# LOOP_DAC.net
KiCad netlist of a schematic drawn in Altium Designer
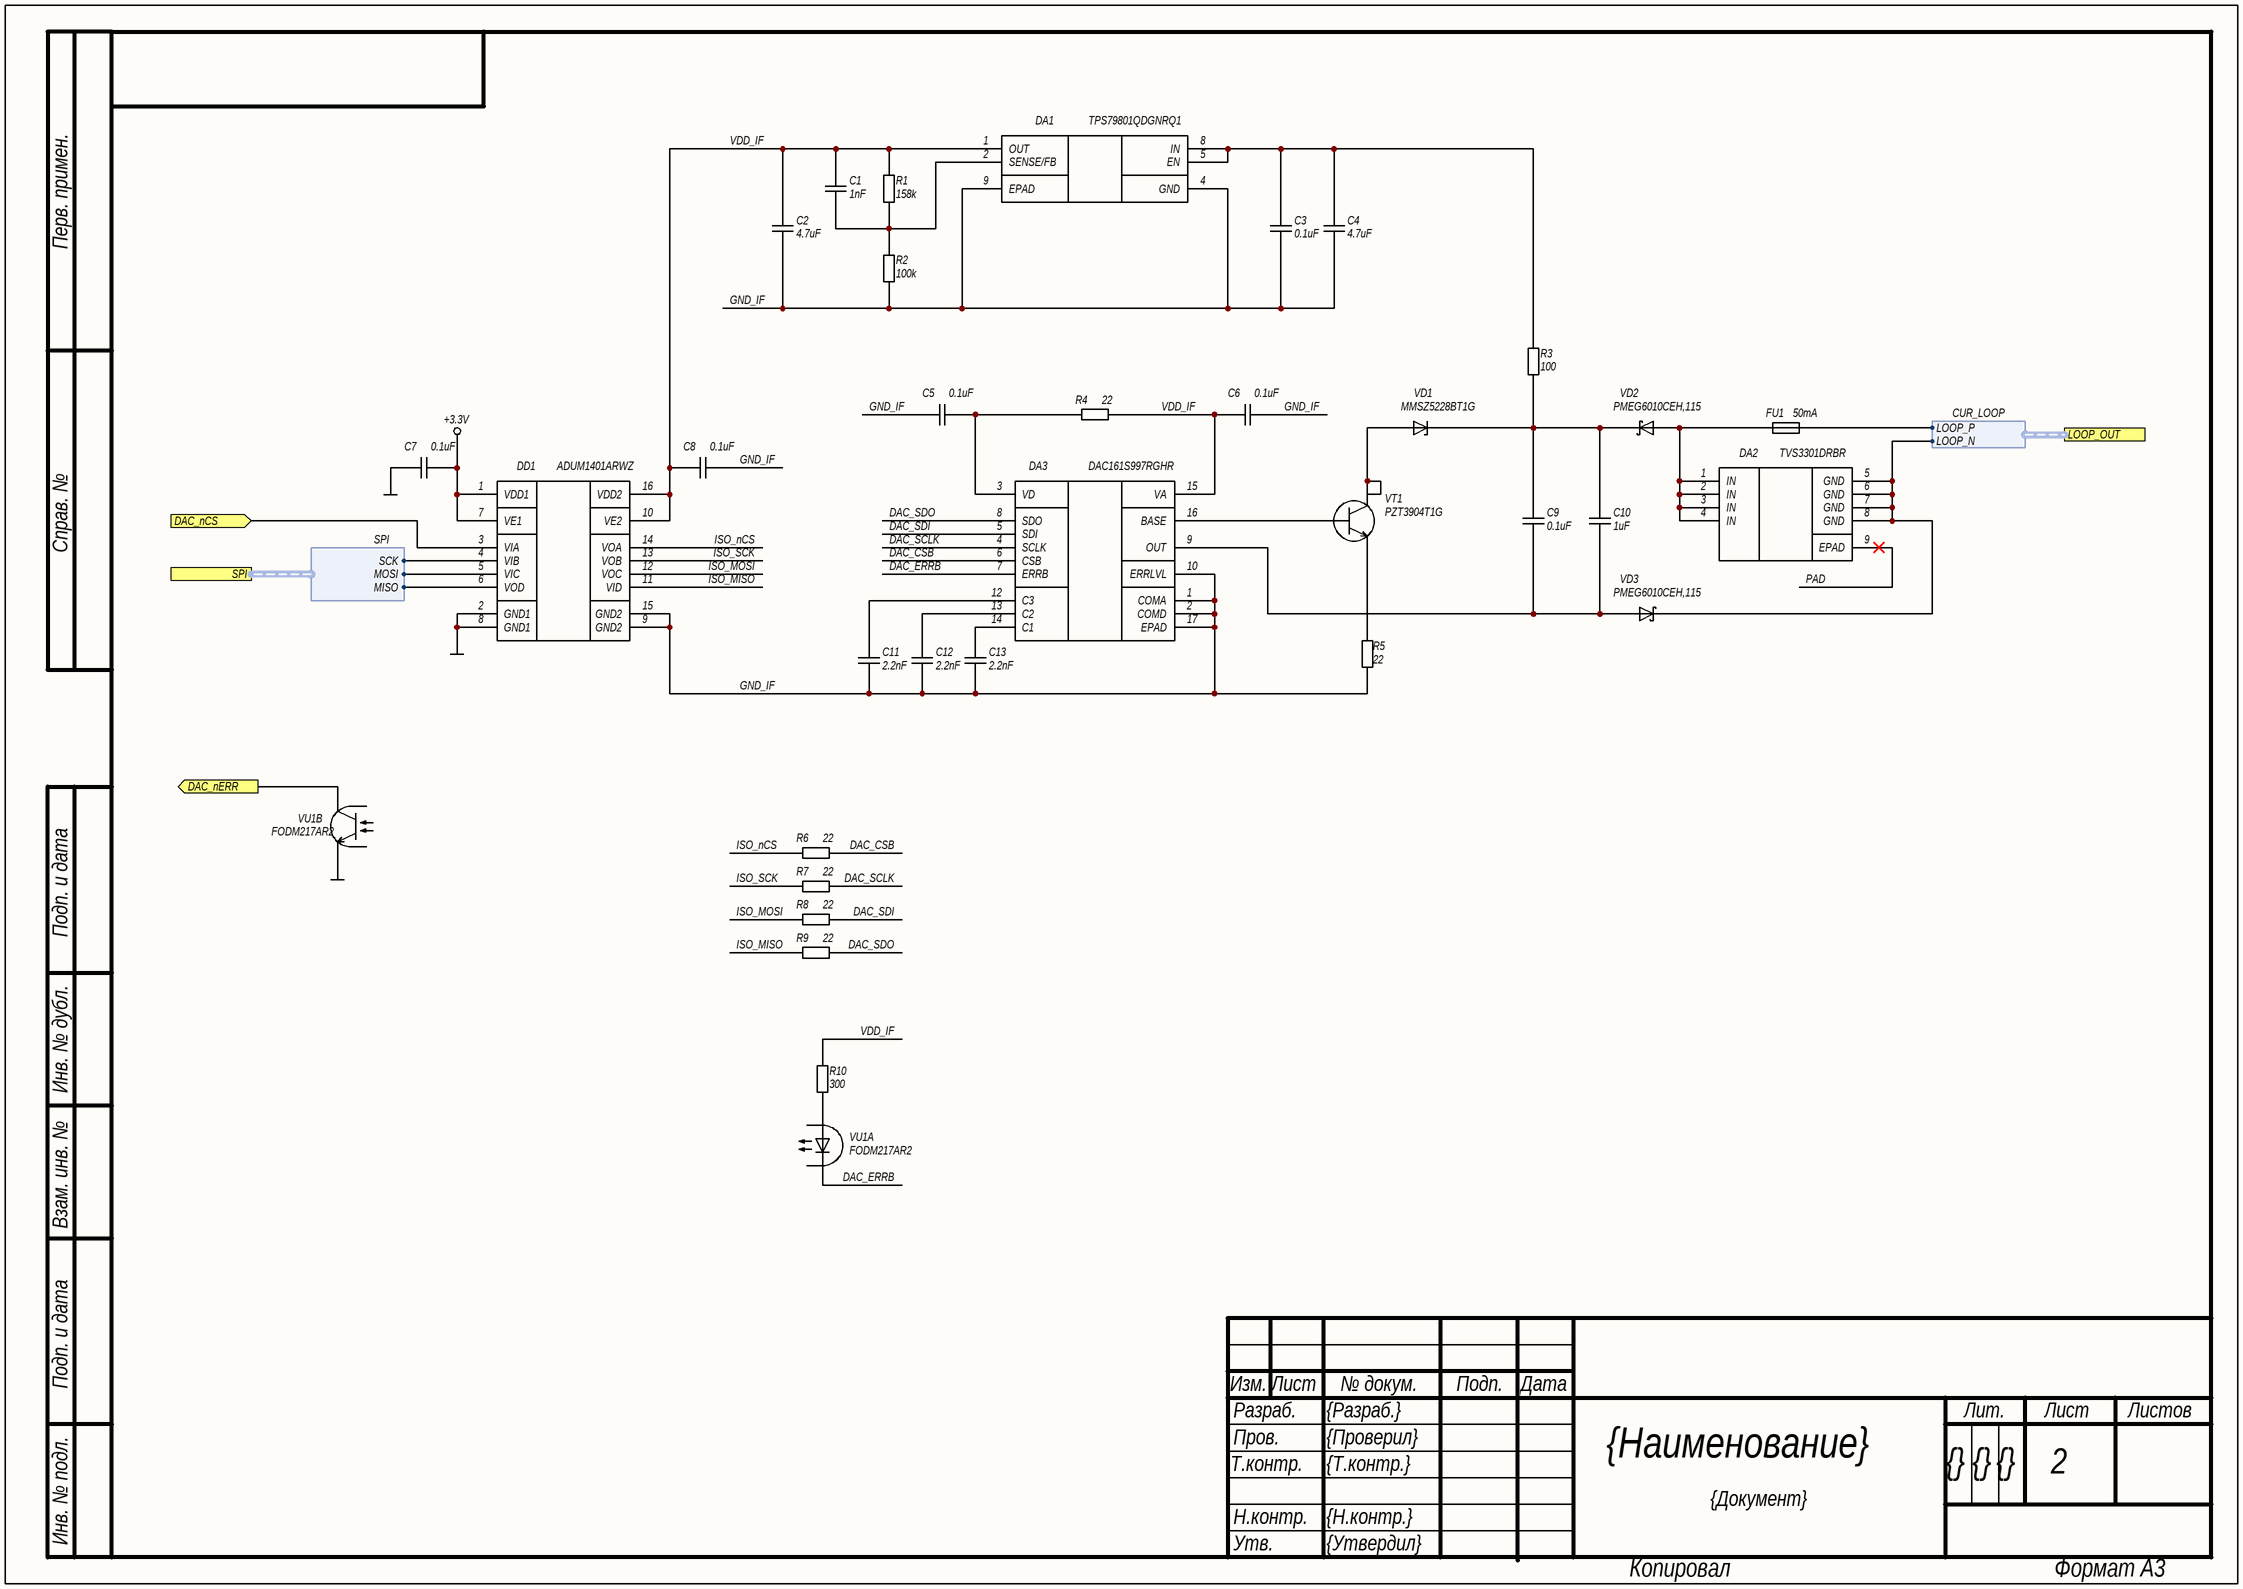
[diagram p0: LOOP_DAC.SchDoc]

(export (version "E")
  (design (tool "Eeschema 10.0.6"))
  (components
    (comp (ref "C1")
      (value "1nF")
      (footprint "C0603N")
      (description "Конденсатор")
      (libsource (lib "Components Library") (part "CAP_FIXED"))
    )
    (comp (ref "C2")
      (value "4.7uF")
      (footprint "C0805N")
      (description "Конденсатор")
      (libsource (lib "Components Library") (part "CAP_FIXED"))
    )
    (comp (ref "C3")
      (value "0.1uF")
      (footprint "C0603N")
      (description "Конденсатор")
      (libsource (lib "Components Library") (part "CAP_FIXED"))
    )
    (comp (ref "C4")
      (value "4.7uF")
      (footprint "C1206N")
      (description "Конденсатор")
      (libsource (lib "Components Library") (part "CAP_FIXED"))
    )
    (comp (ref "C5")
      (value "0.1uF")
      (footprint "C0603N")
      (description "Конденсатор")
      (libsource (lib "Components Library") (part "CAP_FIXED"))
    )
    (comp (ref "C6")
      (value "0.1uF")
      (footprint "C0603N")
      (description "Конденсатор")
      (libsource (lib "Components Library") (part "CAP_FIXED"))
    )
    (comp (ref "C7")
      (value "0.1uF")
      (footprint "C0603N")
      (description "Конденсатор")
      (libsource (lib "Components Library") (part "CAP_FIXED"))
    )
    (comp (ref "C8")
      (value "0.1uF")
      (footprint "C0603N")
      (description "Конденсатор")
      (libsource (lib "Components Library") (part "CAP_FIXED"))
    )
    (comp (ref "C9")
      (value "0.1uF")
      (footprint "C0603N")
      (description "Конденсатор")
      (libsource (lib "Components Library") (part "CAP_FIXED"))
    )
    (comp (ref "C10")
      (value "1uF")
      (footprint "C0603N")
      (description "Конденсатор")
      (libsource (lib "Components Library") (part "CAP_FIXED"))
    )
    (comp (ref "C11")
      (value "2.2nF")
      (footprint "C0603N")
      (description "Конденсатор")
      (libsource (lib "Components Library") (part "CAP_FIXED"))
    )
    (comp (ref "C12")
      (value "2.2nF")
      (footprint "C0603N")
      (description "Конденсатор")
      (libsource (lib "Components Library") (part "CAP_FIXED"))
    )
    (comp (ref "C13")
      (value "2.2nF")
      (footprint "C0603N")
      (description "Конденсатор")
      (libsource (lib "Components Library") (part "CAP_FIXED"))
    )
    (comp (ref "DA1")
      (value "TPS79801QDGNRQ1")
      (footprint "DGN0008B")
      (description "Микросхема линейный стабилизатор напряжения")
      (libsource (lib "Components Library") (part "TPS798xx"))
    )
    (comp (ref "DA2")
      (value "TVS3301DRBR")
      (footprint "DRB0008A")
      (description "Микросхема ограничитель выбросов напряжения")
      (libsource (lib "Components Library") (part "TVS3301"))
    )
    (comp (ref "DA3")
      (value "DAC161S997RGHR")
      (footprint "RGH0016A")
      (description "Микросхема 16-бит ЦАП с токовым выходом 4-20mA")
      (libsource (lib "Components Library") (part "DAC161S997"))
    )
    (comp (ref "DD1")
      (value "ADUM1401ARWZ")
      (footprint "SOIC16_W")
      (description "Микросхема цифровой изолятор интерфейса")
      (libsource (lib "Components Library") (part "ADuM1401"))
    )
    (comp (ref "FU1")
      (value "50mA")
      (footprint "0ZCJ_0.85")
      (description "Плавкий предохранитель")
      (libsource (lib "Components Library") (part "FUSE"))
    )
    (comp (ref "R1")
      (value "158k")
      (footprint "R0603N")
      (description "Резистор")
      (libsource (lib "") (part "RES_FIXED_1"))
    )
    (comp (ref "R2")
      (value "100k")
      (footprint "R0603N")
      (description "Резистор")
      (libsource (lib "") (part "RES_FIXED_1"))
    )
    (comp (ref "R3")
      (value "100")
      (footprint "R0603N")
      (description "Резистор")
      (libsource (lib "") (part "RES_FIXED_1"))
    )
    (comp (ref "R4")
      (value "22")
      (footprint "R0603N")
      (description "Резистор")
      (libsource (lib "Components Library") (part "RES_FIXED"))
    )
    (comp (ref "R5")
      (value "22")
      (footprint "R0603N")
      (description "Резистор")
      (libsource (lib "") (part "RES_FIXED_1"))
    )
    (comp (ref "R6")
      (value "22")
      (footprint "R0603N")
      (description "Резистор")
      (libsource (lib "Components Library") (part "RES_FIXED"))
    )
    (comp (ref "R7")
      (value "22")
      (footprint "R0603N")
      (description "Резистор")
      (libsource (lib "Components Library") (part "RES_FIXED"))
    )
    (comp (ref "R8")
      (value "22")
      (footprint "R0603N")
      (description "Резистор")
      (libsource (lib "Components Library") (part "RES_FIXED"))
    )
    (comp (ref "R9")
      (value "22")
      (footprint "R0603N")
      (description "Резистор")
      (libsource (lib "Components Library") (part "RES_FIXED"))
    )
    (comp (ref "R10")
      (value "300")
      (footprint "R0603N")
      (description "Резистор")
      (libsource (lib "") (part "RES_FIXED_1"))
    )
    (comp (ref "VD1")
      (value "MMSZ5228BT1G")
      (footprint "SOD123")
      (description "Стабилитрон")
      (libsource (lib "Components Library") (part "ZENER"))
    )
    (comp (ref "VD2")
      (value "PMEG6010CEH,115")
      (footprint "SOD123F")
      (description "Диод Шоттки")
      (libsource (lib "Components Library") (part "SCHOTTKY"))
    )
    (comp (ref "VD3")
      (value "PMEG6010CEH,115")
      (footprint "SOD123F")
      (description "Диод Шоттки")
      (libsource (lib "Components Library") (part "SCHOTTKY"))
    )
    (comp (ref "VT1")
      (value "PZT3904T1G")
      (footprint "SOT223")
      (description "Биполярный транзистор, NPN структуры")
      (libsource (lib "Components Library") (part "NPN 4 LEADS_B1"))
    )
    (comp (ref "VU1")
      (value "FODM217AR2")
      (footprint "MFP4 2.5x4.4")
      (description "NPN транзисторная оптопара")
      (libsource (lib "Components Library") (part "OPTOCPL_NPN"))
    )
  )
  (nets
    (net (code "3") (name "+3.3V") (class "Default")
      (node (ref "C7") (pin "1") (pinfunction "1_1") (pintype "passive"))
      (node (ref "DD1") (pin "1") (pinfunction "VDD1_1") (pintype "power_in"))
      (node (ref "DD1") (pin "7") (pinfunction "VE1_7") (pintype "power_in"))
    )
    (net (code "4") (name "/DAC_CSB") (class "Default")
      (node (ref "DA3") (pin "6") (pinfunction "CSB_6") (pintype "power_in"))
      (node (ref "R6") (pin "1") (pinfunction "1_1") (pintype "passive"))
    )
    (net (code "5") (name "/DAC_ERRB") (class "Default")
      (node (ref "DA3") (pin "7") (pinfunction "ERRB_7") (pintype "power_in"))
      (node (ref "VU1") (pin "2") (pinfunction "K_2") (pintype "passive"))
    )
    (net (code "6") (name "/DAC_SCLK") (class "Default")
      (node (ref "DA3") (pin "4") (pinfunction "SCLK_4") (pintype "power_in"))
      (node (ref "R7") (pin "1") (pinfunction "1_1") (pintype "passive"))
    )
    (net (code "7") (name "/DAC_SDI") (class "Default")
      (node (ref "DA3") (pin "5") (pinfunction "SDI_5") (pintype "power_in"))
      (node (ref "R8") (pin "1") (pinfunction "1_1") (pintype "passive"))
    )
    (net (code "8") (name "/DAC_SDO") (class "Default")
      (node (ref "DA3") (pin "8") (pinfunction "SDO_8") (pintype "power_in"))
      (node (ref "R9") (pin "1") (pinfunction "1_1") (pintype "passive"))
    )
    (net (code "9") (name "/DAC_nCS") (class "Default")
      (node (ref "DD1") (pin "3") (pinfunction "VIA_3") (pintype "power_in"))
    )
    (net (code "10") (name "/DAC_nERR") (class "Default")
      (node (ref "VU1") (pin "4") (pinfunction "C_4") (pintype "passive"))
    )
    (net (code "11") (name "/GND_IF") (class "Default")
      (node (ref "C11") (pin "1") (pinfunction "1_1") (pintype "passive"))
      (node (ref "C12") (pin "1") (pinfunction "1_1") (pintype "passive"))
      (node (ref "C13") (pin "1") (pinfunction "1_1") (pintype "passive"))
      (node (ref "C2") (pin "2") (pinfunction "2_2") (pintype "passive"))
      (node (ref "C3") (pin "1") (pinfunction "1_1") (pintype "passive"))
      (node (ref "C4") (pin "2") (pinfunction "2_2") (pintype "passive"))
      (node (ref "C5") (pin "2") (pinfunction "2_2") (pintype "passive"))
      (node (ref "C6") (pin "1") (pinfunction "1_1") (pintype "passive"))
      (node (ref "C8") (pin "1") (pinfunction "1_1") (pintype "passive"))
      (node (ref "DA1") (pin "4") (pinfunction "GND_4") (pintype "passive"))
      (node (ref "DA1") (pin "9") (pinfunction "EPAD_9") (pintype "passive"))
      (node (ref "DA3") (pin "1") (pinfunction "COMA_1") (pintype "power_in"))
      (node (ref "DA3") (pin "10") (pinfunction "ERRLVL_10") (pintype "power_in"))
      (node (ref "DA3") (pin "17") (pinfunction "EPAD_17") (pintype "power_in"))
      (node (ref "DA3") (pin "2") (pinfunction "COMD_2") (pintype "power_in"))
      (node (ref "DD1") (pin "15") (pinfunction "GND2_15") (pintype "power_in"))
      (node (ref "DD1") (pin "9") (pinfunction "GND2_9") (pintype "power_in"))
      (node (ref "R2") (pin "2") (pinfunction "2_2") (pintype "passive"))
      (node (ref "R5") (pin "2") (pinfunction "2_2") (pintype "passive"))
    )
    (net (code "12") (name "/ISO_MISO") (class "Default")
      (node (ref "DD1") (pin "11") (pinfunction "VID_11") (pintype "power_in"))
      (node (ref "R9") (pin "2") (pinfunction "2_2") (pintype "passive"))
    )
    (net (code "13") (name "/ISO_MOSI") (class "Default")
      (node (ref "DD1") (pin "12") (pinfunction "VOC_12") (pintype "power_in"))
      (node (ref "R8") (pin "2") (pinfunction "2_2") (pintype "passive"))
    )
    (net (code "14") (name "/ISO_SCK") (class "Default")
      (node (ref "DD1") (pin "13") (pinfunction "VOB_13") (pintype "power_in"))
      (node (ref "R7") (pin "2") (pinfunction "2_2") (pintype "passive"))
    )
    (net (code "15") (name "/ISO_nCS") (class "Default")
      (node (ref "DD1") (pin "14") (pinfunction "VOA_14") (pintype "power_in"))
      (node (ref "R6") (pin "2") (pinfunction "2_2") (pintype "passive"))
    )
    (net (code "16") (name "/LOOP_N") (class "Default")
      (node (ref "DA2") (pin "5") (pinfunction "GND_5") (pintype "passive"))
      (node (ref "DA2") (pin "6") (pinfunction "GND_6") (pintype "passive"))
      (node (ref "DA2") (pin "7") (pinfunction "GND_7") (pintype "passive"))
      (node (ref "DA2") (pin "8") (pinfunction "GND_8") (pintype "passive"))
      (node (ref "VD3") (pin "1") (pinfunction "K_1") (pintype "passive"))
    )
    (net (code "17") (name "/LOOP_P") (class "Default")
      (node (ref "FU1") (pin "1") (pinfunction "1_1") (pintype "passive"))
    )
    (net (code "18") (name "/MISO") (class "Default")
      (node (ref "DD1") (pin "6") (pinfunction "VOD_6") (pintype "power_in"))
    )
    (net (code "19") (name "/MOSI") (class "Default")
      (node (ref "DD1") (pin "5") (pinfunction "VIC_5") (pintype "power_in"))
    )
    (net (code "20") (name "/PAD") (class "Default")
      (node (ref "DA2") (pin "9") (pinfunction "EPAD_9") (pintype "passive+no_connect"))
    )
    (net (code "21") (name "/SCK") (class "Default")
      (node (ref "DD1") (pin "4") (pinfunction "VIB_4") (pintype "power_in"))
    )
    (net (code "22") (name "/VDD_IF") (class "Default")
      (node (ref "C1") (pin "1") (pinfunction "1_1") (pintype "passive"))
      (node (ref "C2") (pin "1") (pinfunction "1_1") (pintype "passive"))
      (node (ref "C6") (pin "2") (pinfunction "2_2") (pintype "passive"))
      (node (ref "C8") (pin "2") (pinfunction "2_2") (pintype "passive"))
      (node (ref "DA1") (pin "1") (pinfunction "OUT_1") (pintype "passive"))
      (node (ref "DA3") (pin "15") (pinfunction "VA_15") (pintype "power_in"))
      (node (ref "DD1") (pin "10") (pinfunction "VE2_10") (pintype "power_in"))
      (node (ref "DD1") (pin "16") (pinfunction "VDD2_16") (pintype "power_in"))
      (node (ref "R1") (pin "1") (pinfunction "1_1") (pintype "passive"))
      (node (ref "R10") (pin "1") (pinfunction "1_1") (pintype "passive"))
      (node (ref "R4") (pin "1") (pinfunction "1_1") (pintype "passive"))
    )
    (net (code "25") (name "GND") (class "Default")
      (node (ref "C7") (pin "2") (pinfunction "2_2") (pintype "passive"))
      (node (ref "DD1") (pin "2") (pinfunction "GND1_2") (pintype "power_in"))
      (node (ref "DD1") (pin "8") (pinfunction "GND1_8") (pintype "power_in"))
      (node (ref "VU1") (pin "3") (pinfunction "E_3") (pintype "passive"))
    )
    (net (code "26") (name "Net-(DA1-EN)") (class "Default")
      (node (ref "C3") (pin "2") (pinfunction "2_2") (pintype "passive"))
      (node (ref "C4") (pin "1") (pinfunction "1_1") (pintype "passive"))
      (node (ref "DA1") (pin "5") (pinfunction "EN_5") (pintype "passive"))
      (node (ref "DA1") (pin "8") (pinfunction "IN_8") (pintype "passive"))
      (node (ref "R3") (pin "1") (pinfunction "1_1") (pintype "passive"))
    )
    (net (code "27") (name "Net-(DA1-SENSE{slash}FB)") (class "Default")
      (node (ref "C1") (pin "2") (pinfunction "2_2") (pintype "passive"))
      (node (ref "DA1") (pin "2") (pinfunction "SENSE/FB_2") (pintype "passive"))
      (node (ref "R1") (pin "2") (pinfunction "2_2") (pintype "passive"))
      (node (ref "R2") (pin "1") (pinfunction "1_1") (pintype "passive"))
    )
    (net (code "28") (name "Net-(DA3-BASE)") (class "Default")
      (node (ref "DA3") (pin "16") (pinfunction "BASE_16") (pintype "power_in"))
      (node (ref "VT1") (pin "1") (pinfunction "B_1") (pintype "passive"))
    )
    (net (code "29") (name "Net-(DA3-C1)") (class "Default")
      (node (ref "C13") (pin "2") (pinfunction "2_2") (pintype "passive"))
      (node (ref "DA3") (pin "14") (pinfunction "C1_14") (pintype "power_in"))
    )
    (net (code "30") (name "Net-(DA3-C2)") (class "Default")
      (node (ref "C12") (pin "2") (pinfunction "2_2") (pintype "passive"))
      (node (ref "DA3") (pin "13") (pinfunction "C2_13") (pintype "power_in"))
    )
    (net (code "31") (name "Net-(DA3-C3)") (class "Default")
      (node (ref "C11") (pin "2") (pinfunction "2_2") (pintype "passive"))
      (node (ref "DA3") (pin "12") (pinfunction "C3_12") (pintype "power_in"))
    )
    (net (code "32") (name "Net-(DA3-OUT)") (class "Default")
      (node (ref "C10") (pin "2") (pinfunction "2_2") (pintype "passive"))
      (node (ref "C9") (pin "2") (pinfunction "2_2") (pintype "passive"))
      (node (ref "DA3") (pin "9") (pinfunction "OUT_9") (pintype "power_in"))
      (node (ref "VD3") (pin "2") (pinfunction "A_2") (pintype "passive"))
    )
    (net (code "33") (name "Net-(DA3-VD)") (class "Default")
      (node (ref "C5") (pin "1") (pinfunction "1_1") (pintype "passive"))
      (node (ref "DA3") (pin "3") (pinfunction "VD_3") (pintype "power_in"))
      (node (ref "R4") (pin "2") (pinfunction "2_2") (pintype "passive"))
    )
    (net (code "34") (name "Net-(VD1-A)") (class "Default")
      (node (ref "VD1") (pin "2") (pinfunction "A_2") (pintype "passive"))
      (node (ref "VT1") (pin "2") (pinfunction "C_2") (pintype "passive"))
      (node (ref "VT1") (pin "4") (pinfunction "C_4") (pintype "passive"))
    )
    (net (code "35") (name "Net-(VD1-K)") (class "Default")
      (node (ref "C10") (pin "1") (pinfunction "1_1") (pintype "passive"))
      (node (ref "C9") (pin "1") (pinfunction "1_1") (pintype "passive"))
      (node (ref "R3") (pin "2") (pinfunction "2_2") (pintype "passive"))
      (node (ref "VD1") (pin "1") (pinfunction "K_1") (pintype "passive"))
      (node (ref "VD2") (pin "1") (pinfunction "K_1") (pintype "passive"))
    )
    (net (code "36") (name "Net-(VD2-A)") (class "Default")
      (node (ref "DA2") (pin "1") (pinfunction "IN_1") (pintype "passive"))
      (node (ref "DA2") (pin "2") (pinfunction "IN_2") (pintype "passive"))
      (node (ref "DA2") (pin "3") (pinfunction "IN_3") (pintype "passive"))
      (node (ref "DA2") (pin "4") (pinfunction "IN_4") (pintype "passive"))
      (node (ref "FU1") (pin "2") (pinfunction "2_2") (pintype "passive"))
      (node (ref "VD2") (pin "2") (pinfunction "A_2") (pintype "passive"))
    )
    (net (code "37") (name "Net-(VT1-E)") (class "Default")
      (node (ref "R5") (pin "1") (pinfunction "1_1") (pintype "passive"))
      (node (ref "VT1") (pin "3") (pinfunction "E_3") (pintype "passive"))
    )
    (net (code "38") (name "Net-(VU1A-A)") (class "Default")
      (node (ref "R10") (pin "2") (pinfunction "2_2") (pintype "passive"))
      (node (ref "VU1") (pin "1") (pinfunction "A_1") (pintype "passive"))
    )
  )
)
